# pixracer_fmu.net
KiCad netlist of a schematic drawn in Altium Designer
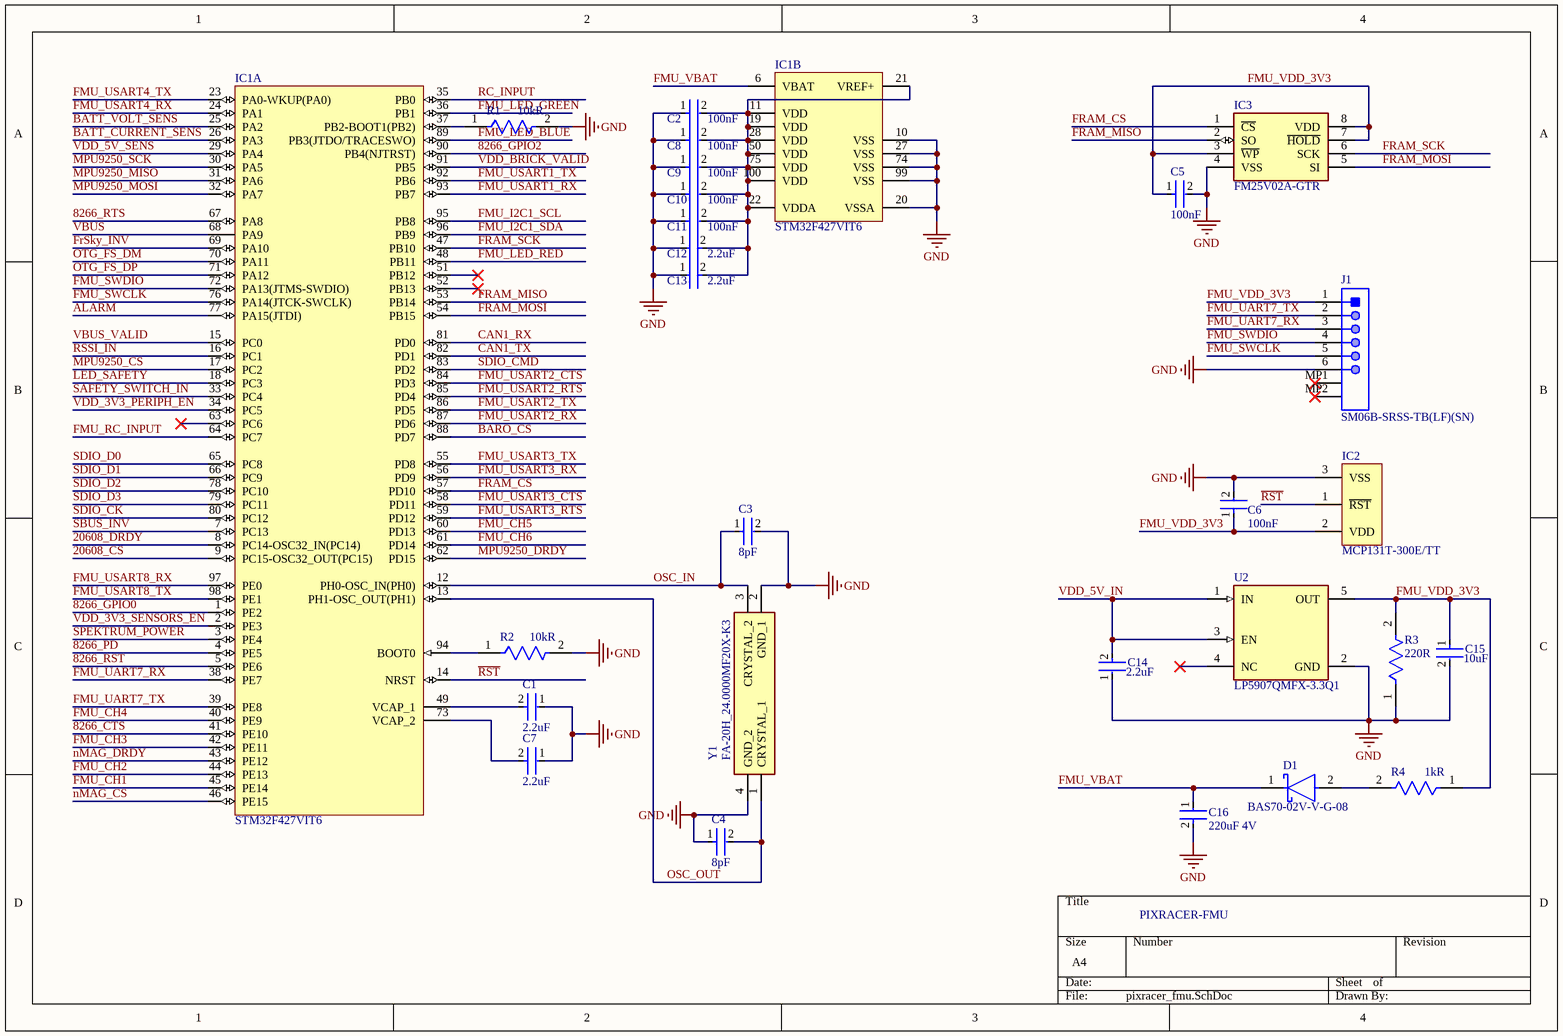
[diagram p0: pixracer_fmu.SchDoc]

(export (version "E")
  (design (tool "Eeschema 10.0.6"))
  (components
    (comp (ref "C1")
      (value "C1608X7R1A225K080AC")
      (footprint "FP-C1608-080-0_1-MFG")
      (description "Multilayer Ceramic Capacitors 2.2μF ±10% 10V X7R SMD 0603")
      (fields (field (name "CAPACITANCE") "2.2uF") (field (name "TOLERANCE") "10%"))
      (libsource (lib "Altium Content Vault") (part "236180d848d6139a670b325ea6854c9"))
    )
    (comp (ref "C2")
      (value "0603ZC104MAT2A")
      (footprint "FP-0603-L_1_6_0_15-W_0_81-IPC_B")
      (description "General Purpose Ceramic Capacitor, 0603, 100nF, 20%, X7R, 15%, 10V")
      (fields (field (name "TOLERANCE") "20%") (field (name "CAPACITANCE") "100nF"))
      (libsource (lib "Altium Content Vault") (part "02cd4be3c70576c341d710602a673aa"))
    )
    (comp (ref "C3")
      (value "CGA3E2C0G1H080D080AA")
      (footprint "FP-CGA3E-0_3-0_1-IPC_A")
      (description "Cap Ceramic 8pF 50V C0G 0.5pF Pad SMD 0603 +125°C Automotive T/R")
      (fields (field (name "CAPACITANCE") "8pF"))
      (libsource (lib "Altium Content Vault") (part "b4654b650e69147ec39a6b967a45e02"))
    )
    (comp (ref "C4")
      (value "CGA3E2C0G1H080D080AA")
      (footprint "FP-CGA3E-0_3-0_1-IPC_A")
      (description "Cap Ceramic 8pF 50V C0G 0.5pF Pad SMD 0603 +125°C Automotive T/R")
      (fields (field (name "CAPACITANCE") "8pF"))
      (libsource (lib "Altium Content Vault") (part "b4654b650e69147ec39a6b967a45e02"))
    )
    (comp (ref "C5")
      (value "0603ZC104MAT2A")
      (footprint "FP-0603-L_1_6_0_15-W_0_81-IPC_B")
      (description "General Purpose Ceramic Capacitor, 0603, 100nF, 20%, X7R, 15%, 10V")
      (fields (field (name "TOLERANCE") "20%") (field (name "CAPACITANCE") "100nF"))
      (libsource (lib "Altium Content Vault") (part "02cd4be3c70576c341d710602a673aa"))
    )
    (comp (ref "C6")
      (value "0603ZC104MAT2A")
      (footprint "FP-0603-L_1_6_0_15-W_0_81-IPC_B")
      (description "General Purpose Ceramic Capacitor, 0603, 100nF, 20%, X7R, 15%, 10V")
      (fields (field (name "TOLERANCE") "20%") (field (name "CAPACITANCE") "100nF"))
      (libsource (lib "Altium Content Vault") (part "02cd4be3c70576c341d710602a673aa"))
    )
    (comp (ref "C7")
      (value "C1608X7R1A225K080AC")
      (footprint "FP-C1608-080-0_1-MFG")
      (description "Multilayer Ceramic Capacitors 2.2μF ±10% 10V X7R SMD 0603")
      (fields (field (name "CAPACITANCE") "2.2uF") (field (name "TOLERANCE") "10%"))
      (libsource (lib "Altium Content Vault") (part "236180d848d6139a670b325ea6854c9"))
    )
    (comp (ref "C8")
      (value "0603ZC104MAT2A")
      (footprint "FP-0603-L_1_6_0_15-W_0_81-IPC_B")
      (description "General Purpose Ceramic Capacitor, 0603, 100nF, 20%, X7R, 15%, 10V")
      (fields (field (name "TOLERANCE") "20%") (field (name "CAPACITANCE") "100nF"))
      (libsource (lib "Altium Content Vault") (part "02cd4be3c70576c341d710602a673aa"))
    )
    (comp (ref "C9")
      (value "0603ZC104MAT2A")
      (footprint "FP-0603-L_1_6_0_15-W_0_81-IPC_B")
      (description "General Purpose Ceramic Capacitor, 0603, 100nF, 20%, X7R, 15%, 10V")
      (fields (field (name "TOLERANCE") "20%") (field (name "CAPACITANCE") "100nF"))
      (libsource (lib "Altium Content Vault") (part "02cd4be3c70576c341d710602a673aa"))
    )
    (comp (ref "C10")
      (value "0603ZC104MAT2A")
      (footprint "FP-0603-L_1_6_0_15-W_0_81-IPC_B")
      (description "General Purpose Ceramic Capacitor, 0603, 100nF, 20%, X7R, 15%, 10V")
      (fields (field (name "TOLERANCE") "20%") (field (name "CAPACITANCE") "100nF"))
      (libsource (lib "Altium Content Vault") (part "02cd4be3c70576c341d710602a673aa"))
    )
    (comp (ref "C11")
      (value "0603ZC104MAT2A")
      (footprint "FP-0603-L_1_6_0_15-W_0_81-IPC_B")
      (description "General Purpose Ceramic Capacitor, 0603, 100nF, 20%, X7R, 15%, 10V")
      (fields (field (name "TOLERANCE") "20%") (field (name "CAPACITANCE") "100nF"))
      (libsource (lib "Altium Content Vault") (part "02cd4be3c70576c341d710602a673aa"))
    )
    (comp (ref "C12")
      (value "C1608X7R1A225K080AC")
      (footprint "FP-C1608-080-0_1-MFG")
      (description "Multilayer Ceramic Capacitors 2.2μF ±10% 10V X7R SMD 0603")
      (fields (field (name "CAPACITANCE") "2.2uF") (field (name "TOLERANCE") "10%"))
      (libsource (lib "Altium Content Vault") (part "236180d848d6139a670b325ea6854c9"))
    )
    (comp (ref "C13")
      (value "C1608X7R1A225K080AC")
      (footprint "FP-C1608-080-0_1-MFG")
      (description "Multilayer Ceramic Capacitors 2.2μF ±10% 10V X7R SMD 0603")
      (fields (field (name "CAPACITANCE") "2.2uF") (field (name "TOLERANCE") "10%"))
      (libsource (lib "Altium Content Vault") (part "236180d848d6139a670b325ea6854c9"))
    )
    (comp (ref "C14")
      (value "C1608X7R1A225K080AC")
      (footprint "FP-C1608-080-0_1-MFG")
      (description "Multilayer Ceramic Capacitors 2.2μF ±10% 10V X7R SMD 0603")
      (fields (field (name "CAPACITANCE") "2.2uF") (field (name "TOLERANCE") "10%"))
      (libsource (lib "Altium Content Vault") (part "236180d848d6139a670b325ea6854c9"))
    )
    (comp (ref "C15")
      (value "CL10A106KP8NNND")
      (footprint "FP-CL10-IPC_B")
      (description "Cap Ceramic 10uF 10V X5R ±10% Pad SMD 0603 +85°C T/R")
      (fields (field (name "TOLERANCE") "10%") (field (name "CAPACITANCE") "10uF"))
      (libsource (lib "Altium Content Vault") (part "b4654b650e69147ec39a6b967a45e02"))
    )
    (comp (ref "C16")
      (value "GRM31CR60G227ME11L")
      (footprint "FP-GRM31C-0_3-e0_3_0_9-IPC_C")
      (description "Chip Multilayer Ceramic Capacitors for General Purpose, 1206, 220uF, X5R, 15%, 20%, 4V")
      (fields (field (name "CAPACITANCE") "220uF 4V") (field (name "TOLERANCE") "20%"))
      (libsource (lib "Altium Content Vault") (part "f23184f103b6ebe33a8c269c53dcba6"))
    )
    (comp (ref "D1")
      (value "BAS70-02V-V-G-08")
      (footprint "FP-S8-V-3880_02-001-MFG")
      (description "DIODE SCHOTTKY 70V 100MA SOD523")
      (fields
        (field (name "OCTOPART") "https://octopart.com/bas70-02v-v-g-08-vishay-44351226")
        (field (name "MANUFACTURER") "Vishay")
      )
      (libsource (lib "Altium Content Vault") (part "1d6ec82d83fb6aee721767c19dac4b9"))
    )
    (comp (ref "IC1")
      (value "STM32F427VIT6")
      (footprint "STM-LQFP100_N")
      (fields (field (name "MANUFACTURER") "STMicroelectronics"))
      (libsource (lib "Altium Content Vault") (part "MC-ARM-STM32F4X7-SQ100"))
    )
    (comp (ref "IC2")
      (value "MCP131T-300E/TT")
      (footprint "SOT-23-TT3_N")
      (description "Micropower Voltage Supervisors, 3-Pin SOT-23, Extended Temperature, Tape and Reel")
      (libsource (lib "Altium Content Vault") (part "PM-SCCT-MCP121-3"))
    )
    (comp (ref "IC3")
      (value "FM25V02A-GTR")
      (footprint "SamacSys:SOIC127P602X173-8N")
      (description "Integrated Circuit")
      (fields (field (name "MOUSER PART NUMBER") "727-FM25V02A-GTR"))
      (libsource (lib "*") (part "FM25V02A-GTR"))
    )
    (comp (ref "J1")
      (value "SM06B-SRSS-TB(LF)(SN)")
      (footprint "JST-SM06B-SRSS-TB_V")
      (description "Male Header, Pitch 1 mm, 1 x 6 Position, Height 2.95 mm, -25 to 85 degC, RoHS, Tape and Reel")
      (fields (field (name "MANUFACTURER") "JST"))
      (libsource (lib "Altium Content Vault") (part "CN-1P-2M-R6"))
    )
    (comp (ref "R1")
      (value "ERJ-3GEYJ103V")
      (footprint "FP-ERJ3G-IPC_C")
      (description "RES SMD 10K OHM 5% 1/10W 0603")
      (fields (field (name "TOLERANCE") "5%") (field (name "RESISTANCE") "10kR"))
      (libsource (lib "Altium Content Vault") (part "1029c3af85768c4190bb7ad29bc67b5"))
    )
    (comp (ref "R2")
      (value "ERJ-3GEYJ103V")
      (footprint "FP-ERJ3G-IPC_C")
      (description "RES SMD 10K OHM 5% 1/10W 0603")
      (fields (field (name "TOLERANCE") "5%") (field (name "RESISTANCE") "10kR"))
      (libsource (lib "Altium Content Vault") (part "1029c3af85768c4190bb7ad29bc67b5"))
    )
    (comp (ref "R3")
      (value "CRCW0603220RFKEB")
      (footprint "FP-CRCW0603-e3-MFG")
      (description "RES Thick Film, 220Ω, 1%, 0.1W, 100ppm/°C, 0603")
      (fields (field (name "TOLERANCE") "1%") (field (name "RESISTANCE") "220R"))
      (libsource (lib "Altium Content Vault") (part "1029c3af85768c4190bb7ad29bc67b5"))
    )
    (comp (ref "R4")
      (value "RC1608J102CS")
      (footprint "FP-RC1608-IPC_A")
      (description "Res Thick Film 0603 1kΩ 5% 0.1W ±100ppm/°C Molded SMD T/R")
      (fields (field (name "RESISTANCE") "1kR") (field (name "TOLERANCE") "5%"))
      (libsource (lib "Altium Content Vault") (part "1029c3af85768c4190bb7ad29bc67b5"))
    )
    (comp (ref "U2")
      (value "LP5907QMFX-3.3Q1")
      (footprint "FP-DBV0005A-MFG")
      (description "IC REG LINEAR 3.3V 250MA SOT23-5")
      (fields
        (field (name "MANUFACTURER") "Texas Instruments")
        (field (name "OCTOPART") "https://octopart.com/lp5907qmfx-3.3q1-texas+instruments-50417899")
      )
      (libsource (lib "Altium Content Vault") (part "e6eddeb8bab6a4ee265087e5808ab9f"))
    )
    (comp (ref "Y1")
      (value "FA-20H_24.0000MF20X-K3")
      (footprint "SamacSys:FA20H160000MF12ZAC3")
      (description "Crystal or Oscillator")
      (fields
        (field (name "MANUFACTURER_PART_NUMBER") "FA-20H 24.0000MF20X-K3")
        (field (name "MOUSER PART NUMBER") "732-FA20H-24F20X-K3")
      )
      (libsource (lib "*") (part "FA-20H_24.0000MF20X-K3"))
    )
  )
  (nets
    (net (code "1") (name "/8266_CTS") (class "Default")
      (node (ref "IC1") (pin "41") (pinfunction "PE10_41") (pintype "bidirectional"))
    )
    (net (code "2") (name "/8266_GPIO0") (class "Default")
      (node (ref "IC1") (pin "1") (pinfunction "PE2_1") (pintype "bidirectional"))
    )
    (net (code "3") (name "/8266_GPIO2") (class "Default")
      (node (ref "IC1") (pin "90") (pinfunction "PB4(NJTRST)_90") (pintype "bidirectional"))
    )
    (net (code "4") (name "/8266_PD") (class "Default")
      (node (ref "IC1") (pin "4") (pinfunction "PE5_4") (pintype "bidirectional"))
    )
    (net (code "5") (name "/8266_RST") (class "Default")
      (node (ref "IC1") (pin "5") (pinfunction "PE6_5") (pintype "bidirectional"))
    )
    (net (code "6") (name "/8266_RTS") (class "Default")
      (node (ref "IC1") (pin "67") (pinfunction "PA8_67") (pintype "bidirectional"))
    )
    (net (code "7") (name "/20608_CS") (class "Default")
      (node (ref "IC1") (pin "9") (pinfunction "PC15-OSC32_OUT(PC15)_9") (pintype "bidirectional"))
    )
    (net (code "8") (name "/20608_DRDY") (class "Default")
      (node (ref "IC1") (pin "8") (pinfunction "PC14-OSC32_IN(PC14)_8") (pintype "bidirectional"))
    )
    (net (code "9") (name "/ALARM") (class "Default")
      (node (ref "IC1") (pin "77") (pinfunction "PA15(JTDI)_77") (pintype "bidirectional"))
    )
    (net (code "10") (name "/BARO_CS") (class "Default")
      (node (ref "IC1") (pin "88") (pinfunction "PD7_88") (pintype "bidirectional"))
    )
    (net (code "11") (name "/BATT_CURRENT_SENS") (class "Default")
      (node (ref "IC1") (pin "26") (pinfunction "PA3_26") (pintype "bidirectional"))
    )
    (net (code "12") (name "/BATT_VOLT_SENS") (class "Default")
      (node (ref "IC1") (pin "25") (pinfunction "PA2_25") (pintype "bidirectional"))
    )
    (net (code "13") (name "/CAN1_RX") (class "Default")
      (node (ref "IC1") (pin "81") (pinfunction "PD0_81") (pintype "bidirectional"))
    )
    (net (code "14") (name "/CAN1_TX") (class "Default")
      (node (ref "IC1") (pin "82") (pinfunction "PD1_82") (pintype "bidirectional"))
    )
    (net (code "15") (name "/FMU_CH1") (class "Default")
      (node (ref "IC1") (pin "45") (pinfunction "PE14_45") (pintype "bidirectional"))
    )
    (net (code "16") (name "/FMU_CH2") (class "Default")
      (node (ref "IC1") (pin "44") (pinfunction "PE13_44") (pintype "bidirectional"))
    )
    (net (code "17") (name "/FMU_CH3") (class "Default")
      (node (ref "IC1") (pin "42") (pinfunction "PE11_42") (pintype "bidirectional"))
    )
    (net (code "18") (name "/FMU_CH4") (class "Default")
      (node (ref "IC1") (pin "40") (pinfunction "PE9_40") (pintype "bidirectional"))
    )
    (net (code "19") (name "/FMU_CH5") (class "Default")
      (node (ref "IC1") (pin "60") (pinfunction "PD13_60") (pintype "bidirectional"))
    )
    (net (code "20") (name "/FMU_CH6") (class "Default")
      (node (ref "IC1") (pin "61") (pinfunction "PD14_61") (pintype "bidirectional"))
    )
    (net (code "21") (name "/FMU_I2C1_SCL") (class "Default")
      (node (ref "IC1") (pin "95") (pinfunction "PB8_95") (pintype "bidirectional"))
    )
    (net (code "22") (name "/FMU_I2C1_SDA") (class "Default")
      (node (ref "IC1") (pin "96") (pinfunction "PB9_96") (pintype "bidirectional"))
    )
    (net (code "23") (name "/FMU_LED_BLUE") (class "Default")
      (node (ref "IC1") (pin "89") (pinfunction "PB3(JTDO/TRACESWO)_89") (pintype "bidirectional"))
    )
    (net (code "24") (name "/FMU_LED_GREEN") (class "Default")
      (node (ref "IC1") (pin "36") (pinfunction "PB1_36") (pintype "bidirectional"))
    )
    (net (code "25") (name "/FMU_LED_RED") (class "Default")
      (node (ref "IC1") (pin "48") (pinfunction "PB11_48") (pintype "bidirectional"))
    )
    (net (code "26") (name "/FMU_RC_INPUT") (class "Default")
      (node (ref "IC1") (pin "64") (pinfunction "PC7_64") (pintype "bidirectional"))
    )
    (net (code "27") (name "/FMU_SWCLK") (class "Default")
      (node (ref "IC1") (pin "76") (pinfunction "PA14(JTCK-SWCLK)_76") (pintype "bidirectional"))
      (node (ref "J1") (pin "5") (pinfunction "5_5") (pintype "passive"))
    )
    (net (code "28") (name "/FMU_SWDIO") (class "Default")
      (node (ref "IC1") (pin "72") (pinfunction "PA13(JTMS-SWDIO)_72") (pintype "bidirectional"))
      (node (ref "J1") (pin "4") (pinfunction "4_4") (pintype "passive"))
    )
    (net (code "29") (name "/FMU_UART7_RX") (class "Default")
      (node (ref "IC1") (pin "38") (pinfunction "PE7_38") (pintype "bidirectional"))
      (node (ref "J1") (pin "3") (pinfunction "3_3") (pintype "passive"))
    )
    (net (code "30") (name "/FMU_UART7_TX") (class "Default")
      (node (ref "IC1") (pin "39") (pinfunction "PE8_39") (pintype "bidirectional"))
      (node (ref "J1") (pin "2") (pinfunction "2_2") (pintype "passive"))
    )
    (net (code "31") (name "/FMU_USART1_RX") (class "Default")
      (node (ref "IC1") (pin "93") (pinfunction "PB7_93") (pintype "bidirectional"))
    )
    (net (code "32") (name "/FMU_USART1_TX") (class "Default")
      (node (ref "IC1") (pin "92") (pinfunction "PB6_92") (pintype "bidirectional"))
    )
    (net (code "33") (name "/FMU_USART2_CTS") (class "Default")
      (node (ref "IC1") (pin "84") (pinfunction "PD3_84") (pintype "bidirectional"))
    )
    (net (code "34") (name "/FMU_USART2_RTS") (class "Default")
      (node (ref "IC1") (pin "85") (pinfunction "PD4_85") (pintype "bidirectional"))
    )
    (net (code "35") (name "/FMU_USART2_RX") (class "Default")
      (node (ref "IC1") (pin "87") (pinfunction "PD6_87") (pintype "bidirectional"))
    )
    (net (code "36") (name "/FMU_USART2_TX") (class "Default")
      (node (ref "IC1") (pin "86") (pinfunction "PD5_86") (pintype "bidirectional"))
    )
    (net (code "37") (name "/FMU_USART3_CTS") (class "Default")
      (node (ref "IC1") (pin "58") (pinfunction "PD11_58") (pintype "bidirectional"))
    )
    (net (code "38") (name "/FMU_USART3_RTS") (class "Default")
      (node (ref "IC1") (pin "59") (pinfunction "PD12_59") (pintype "bidirectional"))
    )
    (net (code "39") (name "/FMU_USART3_RX") (class "Default")
      (node (ref "IC1") (pin "56") (pinfunction "PD9_56") (pintype "bidirectional"))
    )
    (net (code "40") (name "/FMU_USART3_TX") (class "Default")
      (node (ref "IC1") (pin "55") (pinfunction "PD8_55") (pintype "bidirectional"))
    )
    (net (code "41") (name "/FMU_USART4_RX") (class "Default")
      (node (ref "IC1") (pin "24") (pinfunction "PA1_24") (pintype "bidirectional"))
    )
    (net (code "42") (name "/FMU_USART4_TX") (class "Default")
      (node (ref "IC1") (pin "23") (pinfunction "PA0-WKUP(PA0)_23") (pintype "bidirectional"))
    )
    (net (code "43") (name "/FMU_USART8_RX") (class "Default")
      (node (ref "IC1") (pin "97") (pinfunction "PE0_97") (pintype "bidirectional"))
    )
    (net (code "44") (name "/FMU_USART8_TX") (class "Default")
      (node (ref "IC1") (pin "98") (pinfunction "PE1_98") (pintype "bidirectional"))
    )
    (net (code "45") (name "/FMU_VBAT") (class "Default")
      (node (ref "C16") (pin "1") (pinfunction "1_1") (pintype "passive"))
      (node (ref "D1") (pin "1") (pinfunction "C_1") (pintype "passive"))
      (node (ref "IC1") (pin "6") (pinfunction "VBAT_6") (pintype "power_in"))
    )
    (net (code "46") (name "/FMU_VDD_3V3") (class "Default")
      (node (ref "C15") (pin "1") (pinfunction "1_1") (pintype "passive"))
      (node (ref "C5") (pin "1") (pinfunction "1_1") (pintype "passive"))
      (node (ref "C6") (pin "1") (pinfunction "1_1") (pintype "passive"))
      (node (ref "IC2") (pin "2") (pinfunction "VDD_2") (pintype "power_in"))
      (node (ref "IC3") (pin "3") (pinfunction "~{WP}_3") (pintype "passive"))
      (node (ref "IC3") (pin "7") (pinfunction "~{HOLD}_7") (pintype "passive"))
      (node (ref "IC3") (pin "8") (pinfunction "VDD_8") (pintype "passive"))
      (node (ref "J1") (pin "1") (pinfunction "1_1") (pintype "passive"))
      (node (ref "R3") (pin "2") (pinfunction "2_2") (pintype "passive"))
      (node (ref "R4") (pin "1") (pinfunction "1_1") (pintype "passive"))
      (node (ref "U2") (pin "5") (pinfunction "OUT_5") (pintype "power_in"))
    )
    (net (code "47") (name "/FRAM_CS") (class "Default")
      (node (ref "IC1") (pin "57") (pinfunction "PD10_57") (pintype "bidirectional"))
      (node (ref "IC3") (pin "1") (pinfunction "~{CS}_1") (pintype "passive"))
    )
    (net (code "48") (name "/FRAM_MISO") (class "Default")
      (node (ref "IC1") (pin "53") (pinfunction "PB14_53") (pintype "bidirectional"))
      (node (ref "IC3") (pin "2") (pinfunction "SO_2") (pintype "bidirectional"))
    )
    (net (code "49") (name "/FRAM_MOSI") (class "Default")
      (node (ref "IC1") (pin "54") (pinfunction "PB15_54") (pintype "bidirectional"))
      (node (ref "IC3") (pin "5") (pinfunction "SI_5") (pintype "passive"))
    )
    (net (code "50") (name "/FRAM_SCK") (class "Default")
      (node (ref "IC1") (pin "47") (pinfunction "PB10_47") (pintype "bidirectional"))
      (node (ref "IC3") (pin "6") (pinfunction "SCK_6") (pintype "passive"))
    )
    (net (code "51") (name "/FrSky_INV") (class "Default")
      (node (ref "IC1") (pin "69") (pinfunction "PA10_69") (pintype "bidirectional"))
    )
    (net (code "52") (name "/LED_SAFETY") (class "Default")
      (node (ref "IC1") (pin "18") (pinfunction "PC3_18") (pintype "bidirectional"))
    )
    (net (code "53") (name "/MPU9250_CS") (class "Default")
      (node (ref "IC1") (pin "17") (pinfunction "PC2_17") (pintype "bidirectional"))
    )
    (net (code "54") (name "/MPU9250_DRDY") (class "Default")
      (node (ref "IC1") (pin "62") (pinfunction "PD15_62") (pintype "bidirectional"))
    )
    (net (code "55") (name "/MPU9250_MISO") (class "Default")
      (node (ref "IC1") (pin "31") (pinfunction "PA6_31") (pintype "bidirectional"))
    )
    (net (code "56") (name "/MPU9250_MOSI") (class "Default")
      (node (ref "IC1") (pin "32") (pinfunction "PA7_32") (pintype "bidirectional"))
    )
    (net (code "57") (name "/MPU9250_SCK") (class "Default")
      (node (ref "IC1") (pin "30") (pinfunction "PA5_30") (pintype "bidirectional"))
    )
    (net (code "58") (name "/OSC_IN") (class "Default")
      (node (ref "C3") (pin "1") (pinfunction "1_1") (pintype "passive"))
      (node (ref "IC1") (pin "12") (pinfunction "PH0-OSC_IN(PH0)_12") (pintype "bidirectional"))
      (node (ref "Y1") (pin "3") (pinfunction "CRYSTAL_2_3") (pintype "passive"))
    )
    (net (code "59") (name "/OSC_OUT") (class "Default")
      (node (ref "C4") (pin "2") (pinfunction "2_2") (pintype "passive"))
      (node (ref "IC1") (pin "13") (pinfunction "PH1-OSC_OUT(PH1)_13") (pintype "bidirectional"))
      (node (ref "Y1") (pin "1") (pinfunction "CRYSTAL_1_1") (pintype "passive"))
    )
    (net (code "60") (name "/OTG_FS_DM") (class "Default")
      (node (ref "IC1") (pin "70") (pinfunction "PA11_70") (pintype "bidirectional"))
    )
    (net (code "61") (name "/OTG_FS_DP") (class "Default")
      (node (ref "IC1") (pin "71") (pinfunction "PA12_71") (pintype "bidirectional"))
    )
    (net (code "62") (name "/RC_INPUT") (class "Default")
      (node (ref "IC1") (pin "35") (pinfunction "PB0_35") (pintype "bidirectional"))
    )
    (net (code "63") (name "/RSSI_IN") (class "Default")
      (node (ref "IC1") (pin "16") (pinfunction "PC1_16") (pintype "bidirectional"))
    )
    (net (code "64") (name "/SAFETY_SWITCH_IN") (class "Default")
      (node (ref "IC1") (pin "33") (pinfunction "PC4_33") (pintype "bidirectional"))
    )
    (net (code "65") (name "/SBUS_INV") (class "Default")
      (node (ref "IC1") (pin "7") (pinfunction "PC13_7") (pintype "bidirectional"))
    )
    (net (code "66") (name "/SDIO_CK") (class "Default")
      (node (ref "IC1") (pin "80") (pinfunction "PC12_80") (pintype "bidirectional"))
    )
    (net (code "67") (name "/SDIO_CMD") (class "Default")
      (node (ref "IC1") (pin "83") (pinfunction "PD2_83") (pintype "bidirectional"))
    )
    (net (code "68") (name "/SDIO_D0") (class "Default")
      (node (ref "IC1") (pin "65") (pinfunction "PC8_65") (pintype "bidirectional"))
    )
    (net (code "69") (name "/SDIO_D1") (class "Default")
      (node (ref "IC1") (pin "66") (pinfunction "PC9_66") (pintype "bidirectional"))
    )
    (net (code "70") (name "/SDIO_D2") (class "Default")
      (node (ref "IC1") (pin "78") (pinfunction "PC10_78") (pintype "bidirectional"))
    )
    (net (code "71") (name "/SDIO_D3") (class "Default")
      (node (ref "IC1") (pin "79") (pinfunction "PC11_79") (pintype "bidirectional"))
    )
    (net (code "72") (name "/SPEKTRUM_POWER") (class "Default")
      (node (ref "IC1") (pin "3") (pinfunction "PE4_3") (pintype "bidirectional"))
    )
    (net (code "73") (name "/VBUS") (class "Default")
      (node (ref "IC1") (pin "68") (pinfunction "PA9_68") (pintype "bidirectional"))
    )
    (net (code "74") (name "/VBUS_VALID") (class "Default")
      (node (ref "IC1") (pin "15") (pinfunction "PC0_15") (pintype "bidirectional"))
    )
    (net (code "75") (name "/VDD_3V3_PERIPH_EN") (class "Default")
      (node (ref "IC1") (pin "34") (pinfunction "PC5_34") (pintype "bidirectional"))
    )
    (net (code "76") (name "/VDD_3V3_SENSORS_EN") (class "Default")
      (node (ref "IC1") (pin "2") (pinfunction "PE3_2") (pintype "bidirectional"))
    )
    (net (code "77") (name "/VDD_5V_IN") (class "Default")
      (node (ref "C14") (pin "2") (pinfunction "2_2") (pintype "passive"))
      (node (ref "U2") (pin "1") (pinfunction "IN_1") (pintype "input"))
      (node (ref "U2") (pin "3") (pinfunction "EN_3") (pintype "input"))
    )
    (net (code "78") (name "/VDD_5V_SENS") (class "Default")
      (node (ref "IC1") (pin "29") (pinfunction "PA4_29") (pintype "bidirectional"))
    )
    (net (code "79") (name "/VDD_BRICK_VALID") (class "Default")
      (node (ref "IC1") (pin "91") (pinfunction "PB5_91") (pintype "bidirectional"))
    )
    (net (code "80") (name "/nMAG_CS") (class "Default")
      (node (ref "IC1") (pin "46") (pinfunction "PE15_46") (pintype "bidirectional"))
    )
    (net (code "81") (name "/nMAG_DRDY") (class "Default")
      (node (ref "IC1") (pin "43") (pinfunction "PE12_43") (pintype "bidirectional"))
    )
    (net (code "82") (name "/~{RST}") (class "Default")
      (node (ref "IC1") (pin "14") (pinfunction "NRST_14") (pintype "bidirectional"))
      (node (ref "IC2") (pin "1") (pinfunction "~{RST}_1") (pintype "open_collector"))
    )
    (net (code "83") (name "GND") (class "Default")
      (node (ref "C1") (pin "1") (pinfunction "1_1") (pintype "passive"))
      (node (ref "C10") (pin "1") (pinfunction "1_1") (pintype "passive"))
      (node (ref "C11") (pin "1") (pinfunction "1_1") (pintype "passive"))
      (node (ref "C12") (pin "1") (pinfunction "1_1") (pintype "passive"))
      (node (ref "C13") (pin "1") (pinfunction "1_1") (pintype "passive"))
      (node (ref "C14") (pin "1") (pinfunction "1_1") (pintype "passive"))
      (node (ref "C15") (pin "2") (pinfunction "2_2") (pintype "passive"))
      (node (ref "C16") (pin "2") (pinfunction "2_2") (pintype "passive"))
      (node (ref "C2") (pin "1") (pinfunction "1_1") (pintype "passive"))
      (node (ref "C3") (pin "2") (pinfunction "2_2") (pintype "passive"))
      (node (ref "C4") (pin "1") (pinfunction "1_1") (pintype "passive"))
      (node (ref "C5") (pin "2") (pinfunction "2_2") (pintype "passive"))
      (node (ref "C6") (pin "2") (pinfunction "2_2") (pintype "passive"))
      (node (ref "C7") (pin "1") (pinfunction "1_1") (pintype "passive"))
      (node (ref "C8") (pin "1") (pinfunction "1_1") (pintype "passive"))
      (node (ref "C9") (pin "1") (pinfunction "1_1") (pintype "passive"))
      (node (ref "IC1") (pin "10") (pinfunction "VSS_10") (pintype "power_in"))
      (node (ref "IC1") (pin "20") (pinfunction "VSSA_20") (pintype "power_in"))
      (node (ref "IC1") (pin "27") (pinfunction "VSS_27") (pintype "power_in"))
      (node (ref "IC1") (pin "74") (pinfunction "VSS_74") (pintype "power_in"))
      (node (ref "IC1") (pin "99") (pinfunction "VSS_99") (pintype "power_in"))
      (node (ref "IC2") (pin "3") (pinfunction "VSS_3") (pintype "power_in"))
      (node (ref "IC3") (pin "4") (pinfunction "VSS_4") (pintype "passive"))
      (node (ref "J1") (pin "6") (pinfunction "6_6") (pintype "passive"))
      (node (ref "R1") (pin "2") (pinfunction "2_2") (pintype "passive"))
      (node (ref "R2") (pin "2") (pinfunction "2_2") (pintype "passive"))
      (node (ref "R3") (pin "1") (pinfunction "1_1") (pintype "passive"))
      (node (ref "U2") (pin "2") (pinfunction "GND_2") (pintype "power_in"))
      (node (ref "Y1") (pin "2") (pinfunction "GND_1_2") (pintype "passive"))
      (node (ref "Y1") (pin "4") (pinfunction "GND_2_4") (pintype "passive"))
    )
    (net (code "84") (name "Net-(D1-A)") (class "Default")
      (node (ref "D1") (pin "2") (pinfunction "A_2") (pintype "passive"))
      (node (ref "R4") (pin "2") (pinfunction "2_2") (pintype "passive"))
    )
    (net (code "85") (name "Net-(IC1A-BOOT0)") (class "Default")
      (node (ref "IC1") (pin "94") (pinfunction "BOOT0_94") (pintype "input"))
      (node (ref "R2") (pin "1") (pinfunction "1_1") (pintype "passive"))
    )
    (net (code "86") (name "Net-(IC1A-PB2-BOOT1(PB2))") (class "Default")
      (node (ref "IC1") (pin "37") (pinfunction "PB2-BOOT1(PB2)_37") (pintype "bidirectional"))
      (node (ref "R1") (pin "1") (pinfunction "1_1") (pintype "passive"))
    )
    (net (code "87") (name "Net-(IC1A-VCAP_1)") (class "Default")
      (node (ref "C1") (pin "2") (pinfunction "2_2") (pintype "passive"))
      (node (ref "IC1") (pin "49") (pinfunction "VCAP_1_49") (pintype "power_in"))
    )
    (net (code "88") (name "Net-(IC1A-VCAP_2)") (class "Default")
      (node (ref "C7") (pin "2") (pinfunction "2_2") (pintype "passive"))
      (node (ref "IC1") (pin "73") (pinfunction "VCAP_2_73") (pintype "power_in"))
    )
    (net (code "89") (name "Net-(IC1B-VDDA)") (class "Default")
      (node (ref "C10") (pin "2") (pinfunction "2_2") (pintype "passive"))
      (node (ref "C11") (pin "2") (pinfunction "2_2") (pintype "passive"))
      (node (ref "C12") (pin "2") (pinfunction "2_2") (pintype "passive"))
      (node (ref "C13") (pin "2") (pinfunction "2_2") (pintype "passive"))
      (node (ref "C2") (pin "2") (pinfunction "2_2") (pintype "passive"))
      (node (ref "C8") (pin "2") (pinfunction "2_2") (pintype "passive"))
      (node (ref "C9") (pin "2") (pinfunction "2_2") (pintype "passive"))
      (node (ref "IC1") (pin "100") (pinfunction "VDD_100") (pintype "power_in"))
      (node (ref "IC1") (pin "11") (pinfunction "VDD_11") (pintype "power_in"))
      (node (ref "IC1") (pin "19") (pinfunction "VDD_19") (pintype "power_in"))
      (node (ref "IC1") (pin "21") (pinfunction "VREF+_21") (pintype "power_in"))
      (node (ref "IC1") (pin "22") (pinfunction "VDDA_22") (pintype "power_in"))
      (node (ref "IC1") (pin "28") (pinfunction "VDD_28") (pintype "power_in"))
      (node (ref "IC1") (pin "50") (pinfunction "VDD_50") (pintype "power_in"))
      (node (ref "IC1") (pin "75") (pinfunction "VDD_75") (pintype "power_in"))
    )
    (net (code "90") (name "unconnected-(IC1A-PB12-Pad51)") (class "Default")
      (node (ref "IC1") (pin "51") (pinfunction "PB12_51") (pintype "bidirectional+no_connect"))
    )
    (net (code "91") (name "unconnected-(IC1A-PB13-Pad52)") (class "Default")
      (node (ref "IC1") (pin "52") (pinfunction "PB13_52") (pintype "bidirectional+no_connect"))
    )
    (net (code "92") (name "unconnected-(IC1A-PC6-Pad63)") (class "Default")
      (node (ref "IC1") (pin "63") (pinfunction "PC6_63") (pintype "bidirectional+no_connect"))
    )
    (net (code "93") (name "unconnected-(J1-PadMP1)") (class "Default")
      (node (ref "J1") (pin "MP1") (pinfunction "MP1_MP1") (pintype "passive+no_connect"))
    )
    (net (code "94") (name "unconnected-(J1-PadMP2)") (class "Default")
      (node (ref "J1") (pin "MP2") (pinfunction "MP2_MP2") (pintype "passive+no_connect"))
    )
    (net (code "95") (name "unconnected-(U2-NC-Pad4)") (class "Default")
      (node (ref "U2") (pin "4") (pinfunction "NC_4") (pintype "passive+no_connect"))
    )
  )
)
